# rgbw-direct-driver-mk-1_0.net
KiCad netlist of a schematic drawn in EAGLE
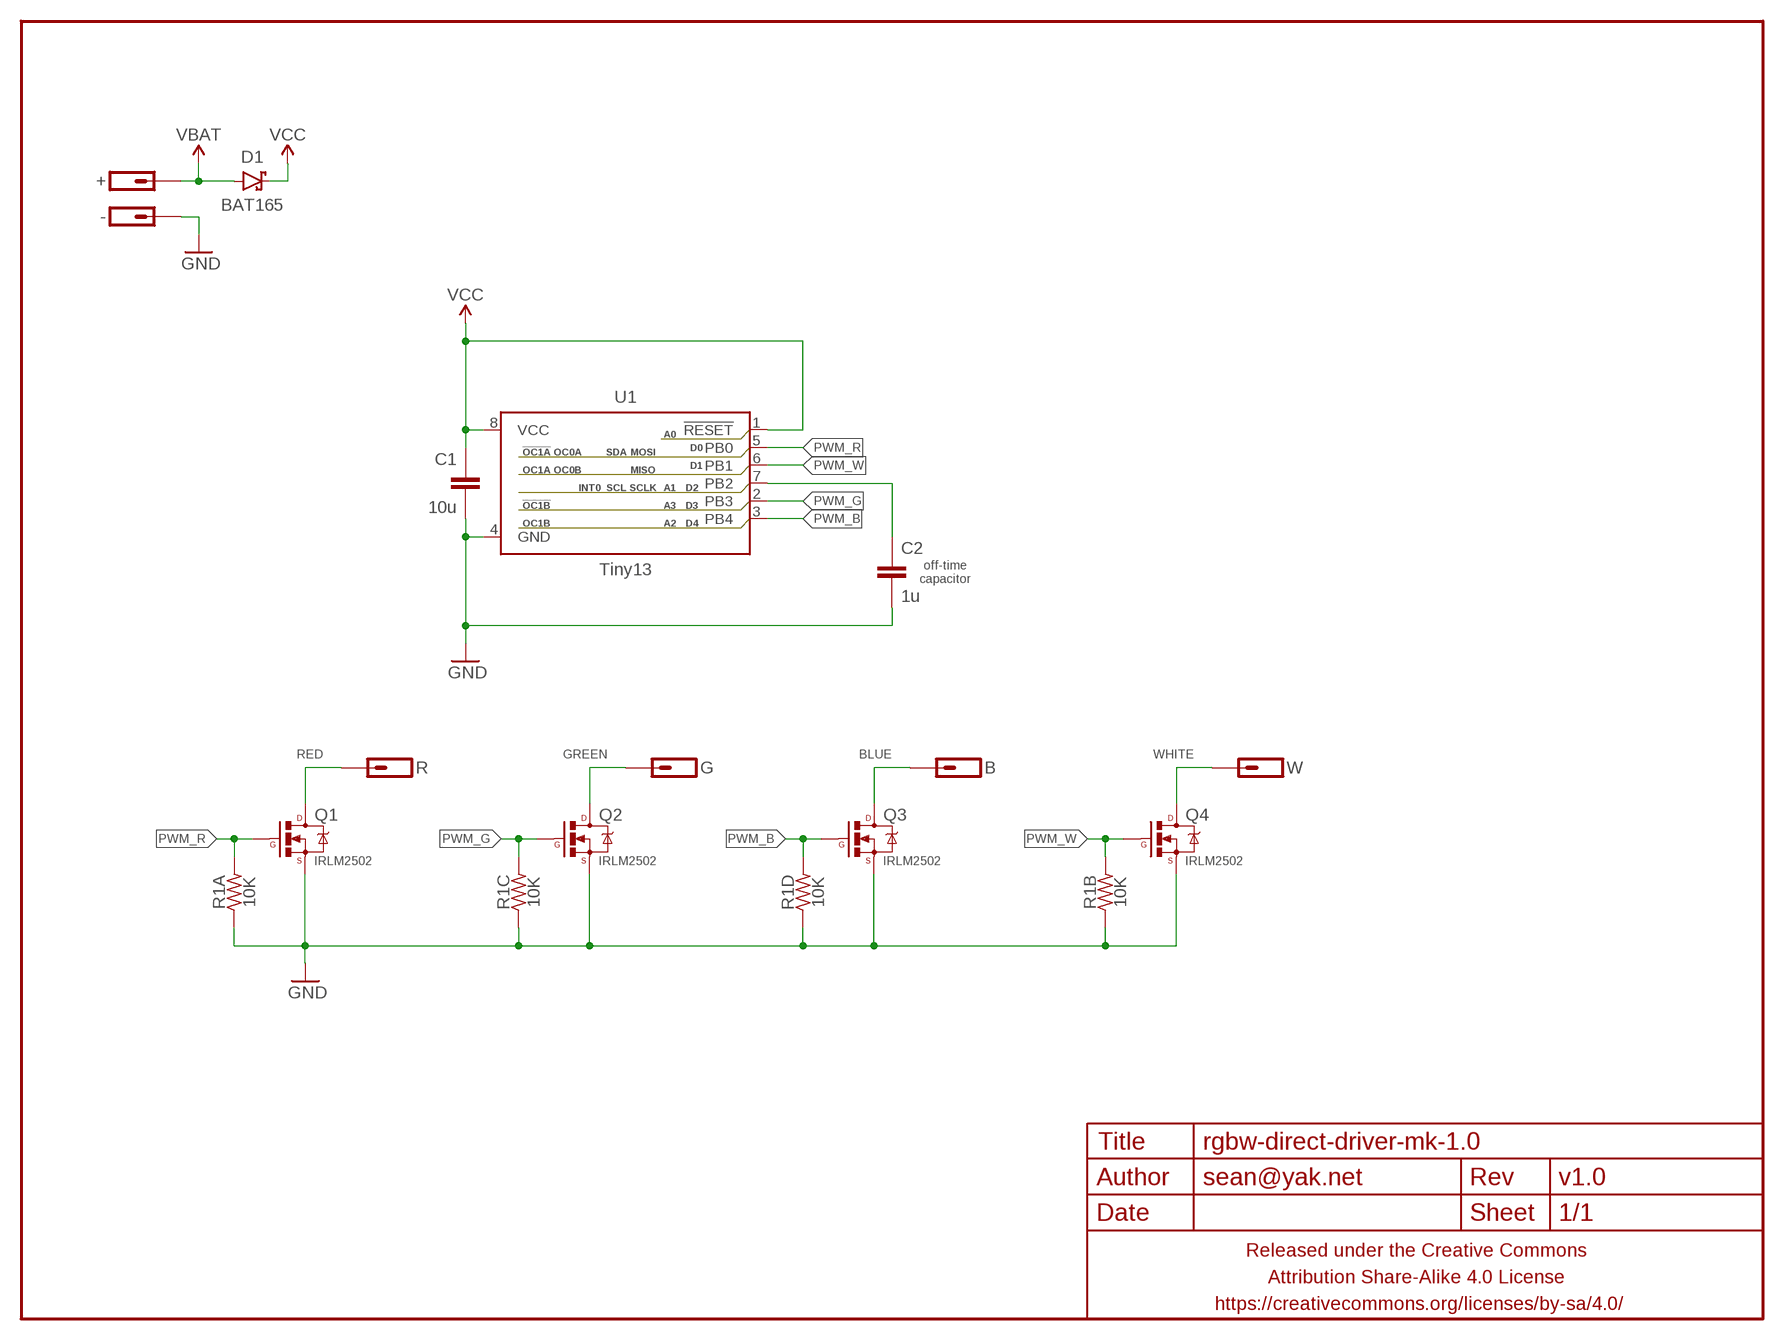
[diagram p0: schematic, sheet 1]

(export (version "E")
  (design (tool "Eeschema 10.0.6"))
  (components
    (comp (ref "+")
      (value "M01PTH-1MM-CIR-NS")
      (footprint "eagle-import:1X01-1MM-CIR-NS")
      (libsource (lib "eagle-import") (part "M01PTH-1MM-CIR-NS"))
    )
    (comp (ref "-")
      (value "M01NOT-A-VIA-NOPE")
      (footprint "eagle-import:1X01_NOSILK_NOSTOP")
      (libsource (lib "eagle-import") (part "M01NOT-A-VIA-NOPE"))
    )
    (comp (ref "B")
      (value "M01SMD-1.25MM-DIA")
      (footprint "eagle-import:1X01-SMD-1.25MM-DIA-NS")
      (libsource (lib "eagle-import") (part "M01SMD-1.25MM-DIA"))
    )
    (comp (ref "C1")
      (value "10u")
      (footprint "eagle-import:C0603-TIGHTER")
      (libsource (lib "eagle-import") (part "CAPACITOR-CERAMICC0603-TIGHTER"))
    )
    (comp (ref "C2")
      (value "1u")
      (footprint "eagle-import:C0402")
      (libsource (lib "eagle-import") (part "CAPACITOR-CERAMICC0402"))
    )
    (comp (ref "D1")
      (value "BAT165")
      (footprint "eagle-import:SOD323-SCHOTTKY")
      (libsource (lib "eagle-import") (part "DIODE-SCHOTTKYSOD323"))
    )
    (comp (ref "FRAME1")
      (value "FRAME-LETTERNO_PACKAGE")
      (footprint "eagle-import:DUMMY")
      (fields (field (name "DESIGNER") "sean@yak.net") (field (name "VERSION") "v1.0"))
      (libsource (lib "eagle-import") (part "FRAME-LETTERNO_PACKAGE"))
    )
    (comp (ref "G")
      (value "M01SMD-1.25MM-DIA")
      (footprint "eagle-import:1X01-SMD-1.25MM-DIA-NS")
      (libsource (lib "eagle-import") (part "M01SMD-1.25MM-DIA"))
    )
    (comp (ref "Q1")
      (value "IRLM2502")
      (footprint "eagle-import:SOT23-CLOSER")
      (libsource (lib "eagle-import") (part "MOSFET-NCHANNELIRLML2502-SMOL"))
    )
    (comp (ref "Q2")
      (value "IRLM2502")
      (footprint "eagle-import:SOT23-CLOSER")
      (libsource (lib "eagle-import") (part "MOSFET-NCHANNELIRLML2502-SMOL"))
    )
    (comp (ref "Q3")
      (value "IRLM2502")
      (footprint "eagle-import:SOT23-CLOSER")
      (libsource (lib "eagle-import") (part "MOSFET-NCHANNELIRLML2502-SMOL"))
    )
    (comp (ref "Q4")
      (value "IRLM2502")
      (footprint "eagle-import:SOT23-CLOSER")
      (libsource (lib "eagle-import") (part "MOSFET-NCHANNELIRLML2502-SMOL"))
    )
    (comp (ref "R")
      (value "M01SMD-1.25MM-DIA")
      (footprint "eagle-import:1X01-SMD-1.25MM-DIA-NS")
      (libsource (lib "eagle-import") (part "M01SMD-1.25MM-DIA"))
    )
    (comp (ref "R1")
      (value "10K")
      (footprint "eagle-import:R1206-ARRAY-4")
      (libsource (lib "eagle-import") (part "RESISTOR-ARRAY-4YC164"))
    )
    (comp (ref "U1")
      (value "Tiny13")
      (footprint "eagle-import:SO08-NARROWER")
      (libsource (lib "eagle-import") (part "ATTINY13SOIC-NARROWPADS"))
    )
    (comp (ref "W")
      (value "M01SMD-1.25MM-DIA")
      (footprint "eagle-import:1X01-SMD-1.25MM-DIA-NS")
      (libsource (lib "eagle-import") (part "M01SMD-1.25MM-DIA"))
    )
  )
  (nets
    (net (code "1") (name "/BLUE") (class "Default")
      (node (ref "B") (pin "P$1") (pinfunction "1_P$1") (pintype "passive"))
      (node (ref "Q3") (pin "3") (pinfunction "D_3") (pintype "passive"))
    )
    (net (code "2") (name "/GREEN") (class "Default")
      (node (ref "G") (pin "P$1") (pinfunction "1_P$1") (pintype "passive"))
      (node (ref "Q2") (pin "3") (pinfunction "D_3") (pintype "passive"))
    )
    (net (code "3") (name "/RED") (class "Default")
      (node (ref "Q1") (pin "3") (pinfunction "D_3") (pintype "passive"))
      (node (ref "R") (pin "P$1") (pinfunction "1_P$1") (pintype "passive"))
    )
    (net (code "4") (name "/WHITE") (class "Default")
      (node (ref "Q4") (pin "3") (pinfunction "D_3") (pintype "passive"))
      (node (ref "W") (pin "P$1") (pinfunction "1_P$1") (pintype "passive"))
    )
    (net (code "5") (name "GND") (class "Default")
      (node (ref "-") (pin "P$1") (pinfunction "1_P$1") (pintype "passive"))
      (node (ref "C1") (pin "2") (pinfunction "2_2") (pintype "passive"))
      (node (ref "C2") (pin "2") (pinfunction "2_2") (pintype "passive"))
      (node (ref "Q1") (pin "2") (pinfunction "S_2") (pintype "passive"))
      (node (ref "Q2") (pin "2") (pinfunction "S_2") (pintype "passive"))
      (node (ref "Q3") (pin "2") (pinfunction "S_2") (pintype "passive"))
      (node (ref "Q4") (pin "2") (pinfunction "S_2") (pintype "passive"))
      (node (ref "R1") (pin "A1") (pinfunction "1_A1") (pintype "passive"))
      (node (ref "R1") (pin "B1") (pinfunction "1_B1") (pintype "passive"))
      (node (ref "R1") (pin "C1") (pinfunction "1_C1") (pintype "passive"))
      (node (ref "R1") (pin "D1") (pinfunction "1_D1") (pintype "passive"))
      (node (ref "U1") (pin "4") (pinfunction "GND_4") (pintype "bidirectional"))
    )
    (net (code "6") (name "Net-(U1-PB2)") (class "Default")
      (node (ref "C2") (pin "1") (pinfunction "1_1") (pintype "passive"))
      (node (ref "U1") (pin "7") (pinfunction "PB2_7") (pintype "bidirectional"))
    )
    (net (code "7") (name "PWM_B") (class "Default")
      (node (ref "Q3") (pin "1") (pinfunction "G_1") (pintype "passive"))
      (node (ref "R1") (pin "D2") (pinfunction "2_D2") (pintype "passive"))
      (node (ref "U1") (pin "3") (pinfunction "PB4_3") (pintype "bidirectional"))
    )
    (net (code "8") (name "PWM_G") (class "Default")
      (node (ref "Q2") (pin "1") (pinfunction "G_1") (pintype "passive"))
      (node (ref "R1") (pin "C2") (pinfunction "2_C2") (pintype "passive"))
      (node (ref "U1") (pin "2") (pinfunction "PB3_2") (pintype "bidirectional"))
    )
    (net (code "9") (name "PWM_R") (class "Default")
      (node (ref "Q1") (pin "1") (pinfunction "G_1") (pintype "passive"))
      (node (ref "R1") (pin "A2") (pinfunction "2_A2") (pintype "passive"))
      (node (ref "U1") (pin "5") (pinfunction "PB0_5") (pintype "bidirectional"))
    )
    (net (code "10") (name "PWM_W") (class "Default")
      (node (ref "Q4") (pin "1") (pinfunction "G_1") (pintype "passive"))
      (node (ref "R1") (pin "B2") (pinfunction "2_B2") (pintype "passive"))
      (node (ref "U1") (pin "6") (pinfunction "PB1_6") (pintype "bidirectional"))
    )
    (net (code "11") (name "VBAT") (class "Default")
      (node (ref "+") (pin "1") (pinfunction "1_1") (pintype "passive"))
      (node (ref "D1") (pin "A") (pinfunction "A_A") (pintype "passive"))
    )
    (net (code "12") (name "VCC") (class "Default")
      (node (ref "C1") (pin "1") (pinfunction "1_1") (pintype "passive"))
      (node (ref "D1") (pin "C") (pinfunction "C_C") (pintype "passive"))
      (node (ref "U1") (pin "1") (pinfunction "~{RESET}_1") (pintype "bidirectional"))
      (node (ref "U1") (pin "8") (pinfunction "VCC_8") (pintype "bidirectional"))
    )
  )
)
